# StripConnectorUSB64.net
KiCad netlist of a schematic drawn in EAGLE
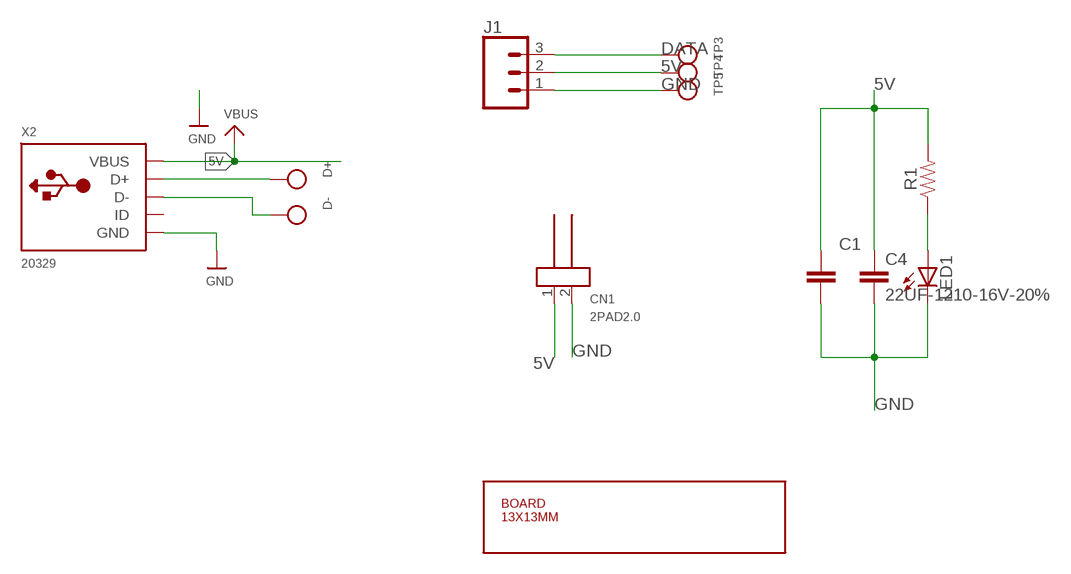
[diagram p0: schematic, sheet 1]

(export (version "E")
  (design (tool "Eeschema 10.0.6"))
  (components
    (comp (ref "C1")
      (value "CAPACITOR_NPOL-0805")
      (footprint "eagle-import:C805")
      (libsource (lib "eagle-import") (part "CAPACITOR_NPOL-0805"))
    )
    (comp (ref "C4")
      (value "22UF-1210-16V-20%")
      (footprint "eagle-import:1210")
      (libsource (lib "eagle-import") (part "22UF-1210-16V-20%"))
    )
    (comp (ref "CN1")
      (value "2PAD2.0")
      (footprint "eagle-import:2POLE_P2.0")
      (libsource (lib "eagle-import") (part "2PAD2.0"))
    )
    (comp (ref "D+")
      (value "TESTPOINTROUND1MM")
      (footprint "eagle-import:TESTPOINT_ROUND_1MM")
      (libsource (lib "eagle-import") (part "TESTPOINTROUND1MM"))
    )
    (comp (ref "D-")
      (value "TESTPOINTROUND1MM")
      (footprint "eagle-import:TESTPOINT_ROUND_1MM")
      (libsource (lib "eagle-import") (part "TESTPOINTROUND1MM"))
    )
    (comp (ref "J1")
      (value "CONN_03LONGPADS")
      (footprint "eagle-import:1X03_LONGPADS")
      (libsource (lib "eagle-import") (part "CONN_03LONGPADS"))
    )
    (comp (ref "LED1")
      (value "LED-0805")
      (footprint "eagle-import:LED-805")
      (libsource (lib "eagle-import") (part "LED-0805"))
    )
    (comp (ref "R1")
      (value "RESISTOR0805")
      (footprint "eagle-import:0805")
      (libsource (lib "eagle-import") (part "RESISTOR0805"))
    )
    (comp (ref "TP3")
      (value "TESTPOINTROUND1MM")
      (footprint "eagle-import:TESTPOINT_ROUND_1MM")
      (libsource (lib "eagle-import") (part "TESTPOINTROUND1MM"))
    )
    (comp (ref "TP4")
      (value "TESTPOINTROUND1MM")
      (footprint "eagle-import:TESTPOINT_ROUND_1MM")
      (libsource (lib "eagle-import") (part "TESTPOINTROUND1MM"))
    )
    (comp (ref "TP5")
      (value "TESTPOINTROUND1MM")
      (footprint "eagle-import:TESTPOINT_ROUND_1MM")
      (libsource (lib "eagle-import") (part "TESTPOINTROUND1MM"))
    )
    (comp (ref "U$1")
      (value "BOARD_13X13MM")
      (footprint "eagle-import:13X13")
      (libsource (lib "eagle-import") (part "BOARD_13X13MM"))
    )
    (comp (ref "X2")
      (value "20329")
      (footprint "eagle-import:4UCONN_20329_V2")
      (libsource (lib "eagle-import") (part "USB_MICRO_20329_V2"))
    )
  )
  (nets
    (net (code "1") (name "/DATA") (class "Default")
      (node (ref "J1") (pin "3") (pinfunction "3_3") (pintype "passive"))
      (node (ref "TP3") (pin "P$1") (pinfunction "P$1_P$1") (pintype "bidirectional"))
    )
    (net (code "2") (name "5V") (class "Default")
      (node (ref "C1") (pin "1") (pinfunction "1_1") (pintype "passive"))
      (node (ref "C4") (pin "1") (pinfunction "1_1") (pintype "passive"))
      (node (ref "CN1") (pin "1") (pinfunction "P$1_1") (pintype "bidirectional"))
      (node (ref "J1") (pin "2") (pinfunction "2_2") (pintype "passive"))
      (node (ref "R1") (pin "2") (pinfunction "2_2") (pintype "passive"))
      (node (ref "TP4") (pin "P$1") (pinfunction "P$1_P$1") (pintype "bidirectional"))
      (node (ref "X2") (pin "VBUS") (pinfunction "VBUS_VBUS") (pintype "power_in"))
    )
    (net (code "3") (name "GND") (class "Default")
      (node (ref "C1") (pin "2") (pinfunction "2_2") (pintype "passive"))
      (node (ref "C4") (pin "2") (pinfunction "2_2") (pintype "passive"))
      (node (ref "CN1") (pin "2") (pinfunction "P$2_2") (pintype "bidirectional"))
      (node (ref "J1") (pin "1") (pinfunction "1_1") (pintype "passive"))
      (node (ref "LED1") (pin "C") (pinfunction "C_C") (pintype "passive"))
      (node (ref "TP5") (pin "P$1") (pinfunction "P$1_P$1") (pintype "bidirectional"))
      (node (ref "X2") (pin "BASE@1") (pinfunction "GND_BASE@1") (pintype "power_in"))
      (node (ref "X2") (pin "BASE@2") (pinfunction "GND_BASE@2") (pintype "power_in"))
      (node (ref "X2") (pin "GND") (pinfunction "GND_GND") (pintype "power_in"))
      (node (ref "X2") (pin "SPRT@1") (pinfunction "GND_SPRT@1") (pintype "power_in"))
      (node (ref "X2") (pin "SPRT@2") (pinfunction "GND_SPRT@2") (pintype "power_in"))
      (node (ref "X2") (pin "SPRT@3") (pinfunction "GND_SPRT@3") (pintype "power_in"))
      (node (ref "X2") (pin "SPRT@4") (pinfunction "GND_SPRT@4") (pintype "power_in"))
    )
    (net (code "4") (name "Net-(D+-PadP$1)") (class "Default")
      (node (ref "D+") (pin "P$1") (pinfunction "P$1_P$1") (pintype "bidirectional"))
      (node (ref "X2") (pin "D+") (pinfunction "D+_D+") (pintype "bidirectional"))
    )
    (net (code "5") (name "Net-(D--PadP$1)") (class "Default")
      (node (ref "D-") (pin "P$1") (pinfunction "P$1_P$1") (pintype "bidirectional"))
      (node (ref "X2") (pin "D-") (pinfunction "D-_D-") (pintype "bidirectional"))
    )
    (net (code "6") (name "Net-(LED1-PadA)") (class "Default")
      (node (ref "LED1") (pin "A") (pinfunction "A_A") (pintype "passive"))
      (node (ref "R1") (pin "1") (pinfunction "1_1") (pintype "passive"))
    )
    (net (code "7") (name "unconnected-(X2-PadID)") (class "Default")
      (node (ref "X2") (pin "ID") (pinfunction "ID_ID") (pintype "bidirectional"))
    )
  )
)
